# Carrier_for-Addons-V01-004.net
KiCad netlist of a schematic drawn in EAGLE
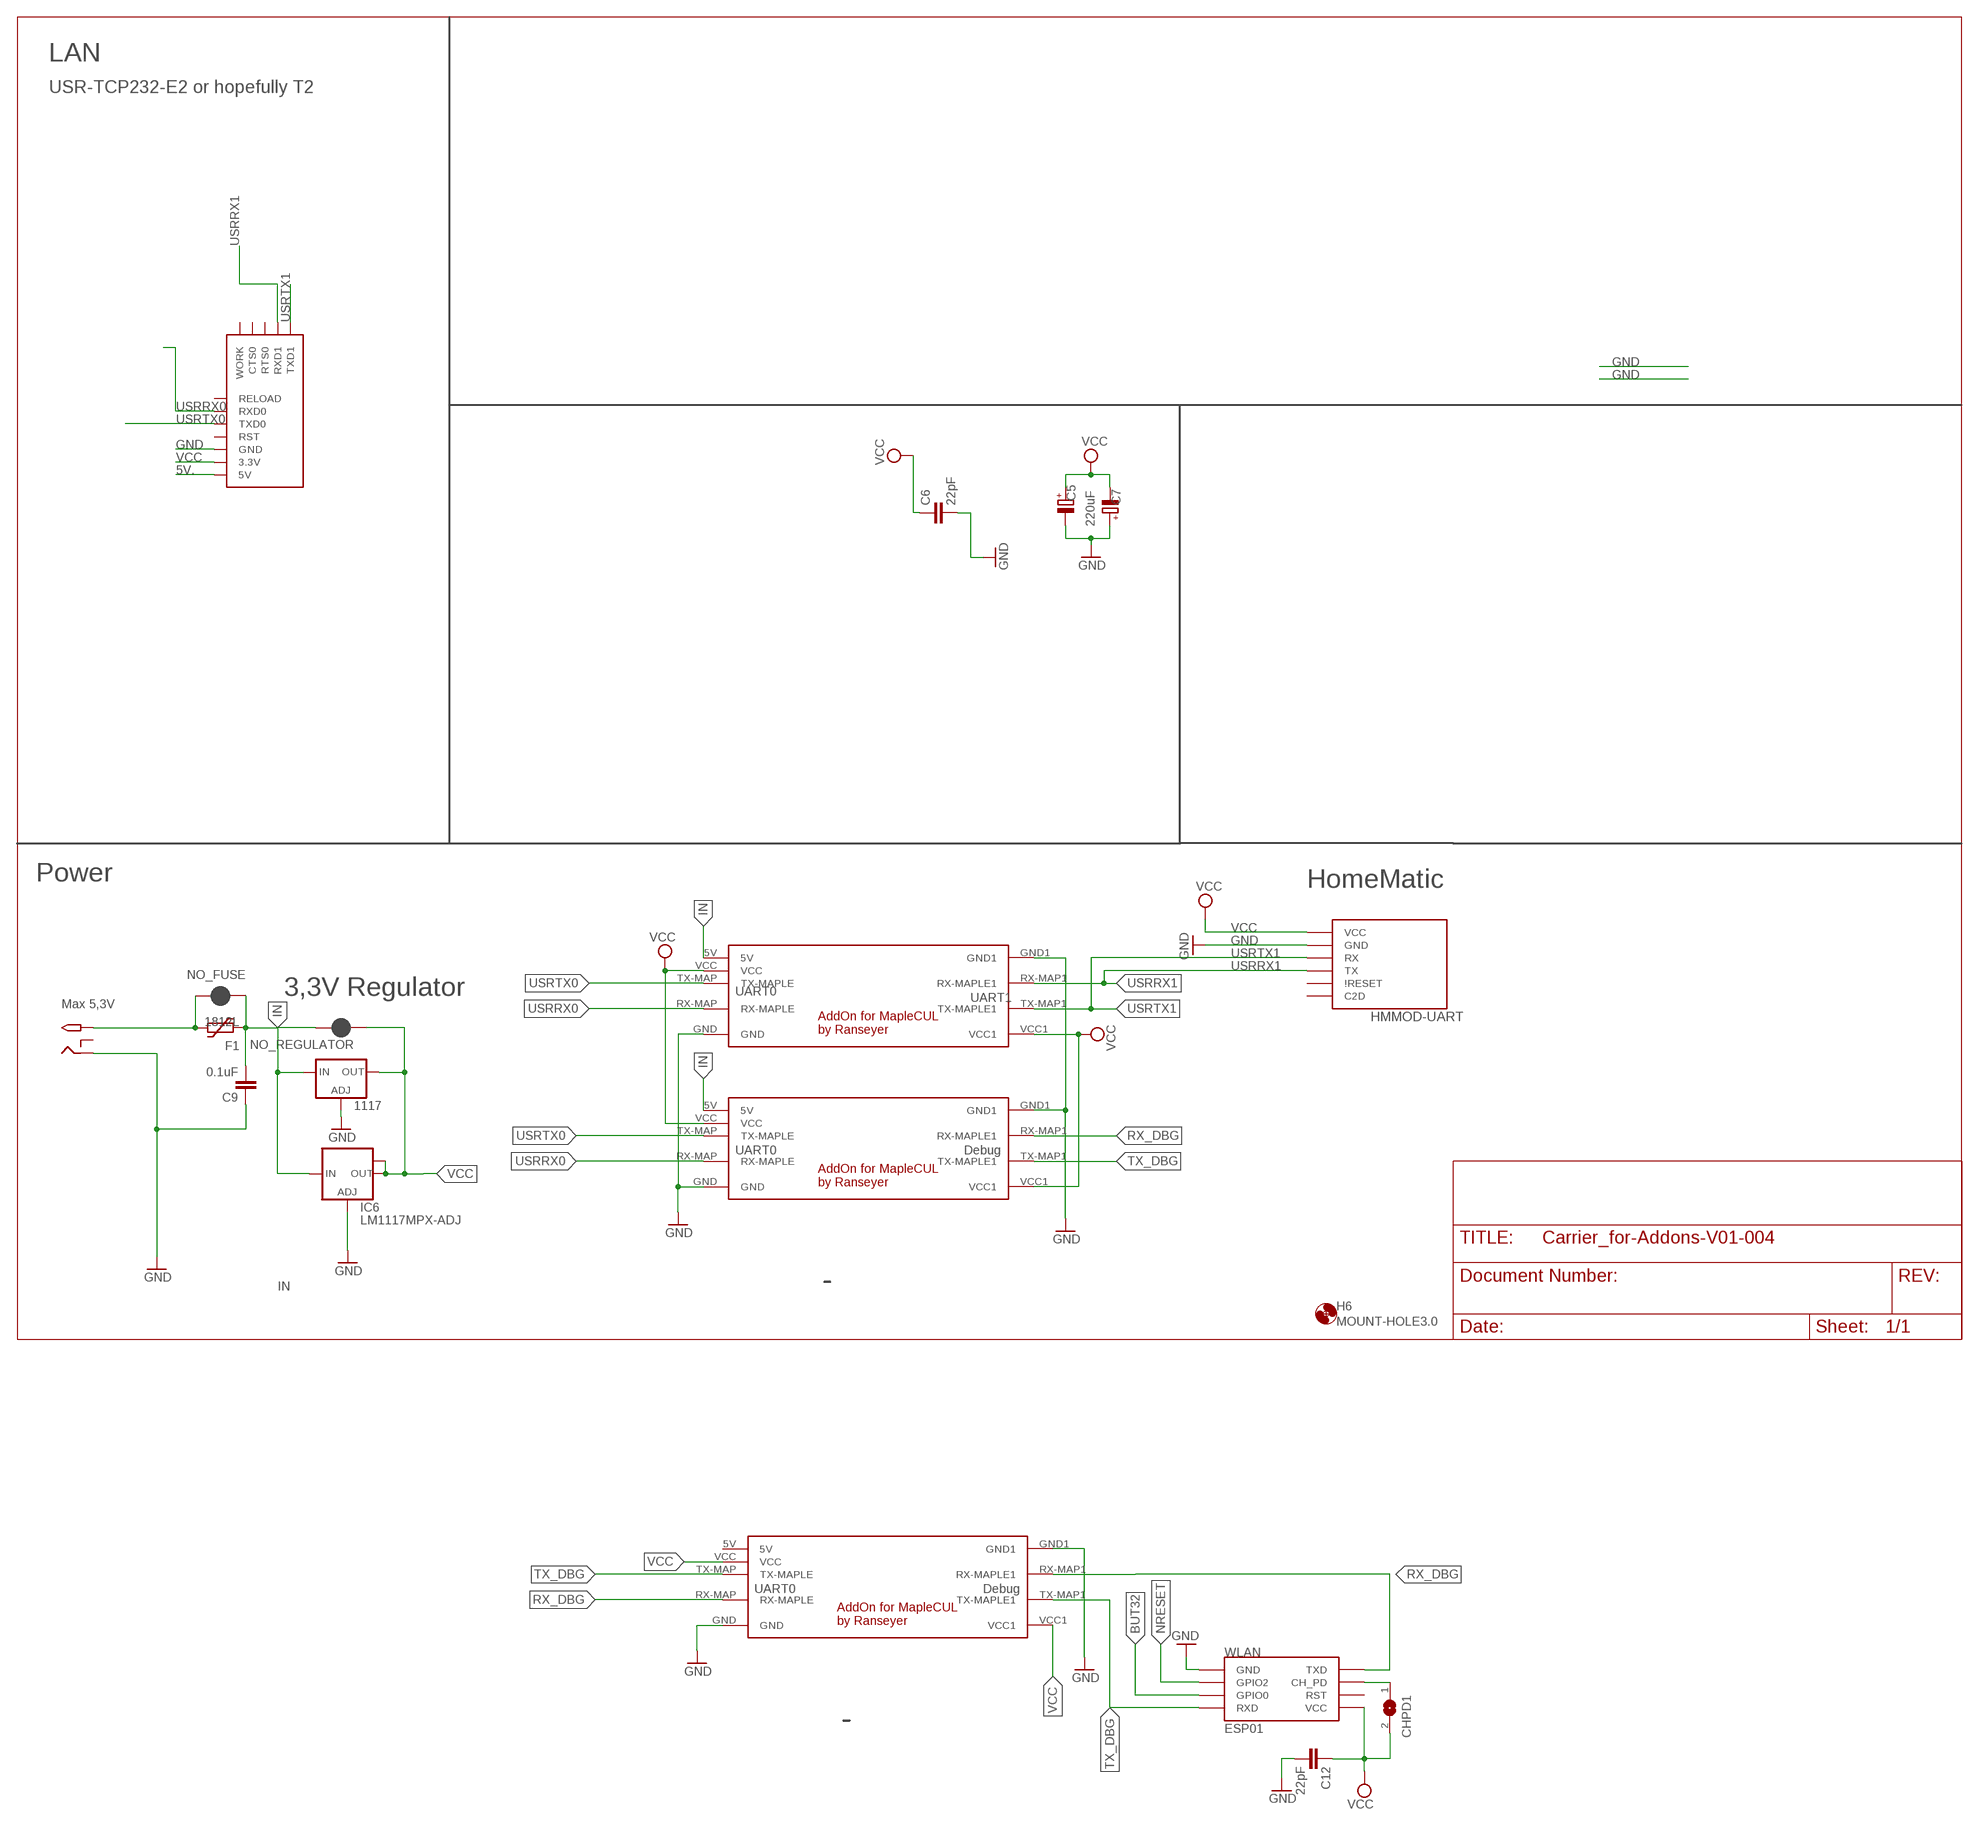
[diagram p0: schematic, sheet 1, part 1 of 2]
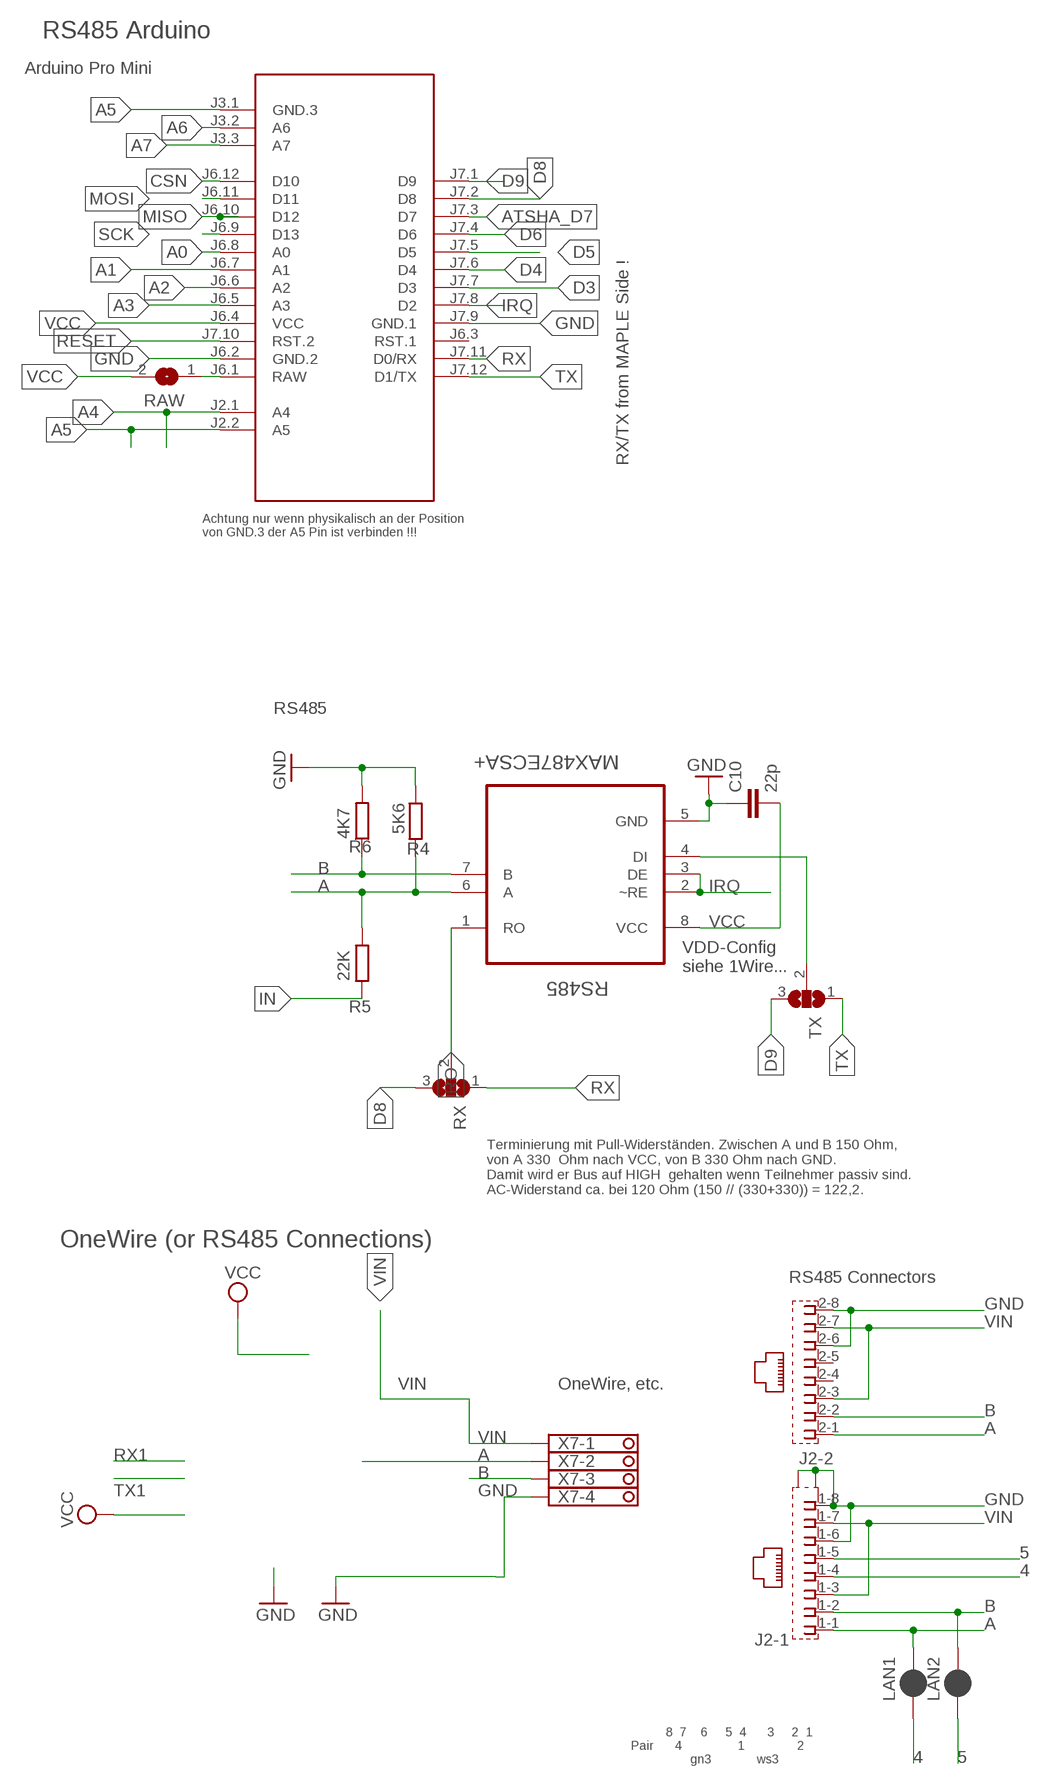
[diagram p1: schematic, sheet 1, part 2 of 2]

(export (version "E")
  (design (tool "Eeschema 10.0.6"))
  (components
    (comp (ref "1117")
      (value "LD117ADT50TR")
      (footprint "eagle-import:DPACK")
      (libsource (lib "eagle-import") (part "LD117A?DT50TR"))
    )
    (comp (ref "C5")
      (value "220uF")
      (footprint "eagle-import:E5-8,5")
      (libsource (lib "eagle-import") (part "CPOL-EUE5-8.5"))
    )
    (comp (ref "C6")
      (value "22pF")
      (footprint "eagle-import:C0805")
      (libsource (lib "eagle-import") (part "C-EUC0805"))
    )
    (comp (ref "C7")
      (value "CPOL-EUSMCE")
      (footprint "eagle-import:SMC_E")
      (libsource (lib "eagle-import") (part "rcl_334_CPOL-EUSMCE"))
    )
    (comp (ref "C9")
      (value "0.1uF")
      (footprint "eagle-import:C1206")
      (libsource (lib "eagle-import") (part "C-EUC1206"))
    )
    (comp (ref "C10")
      (value "22p")
      (footprint "eagle-import:C0805")
      (libsource (lib "eagle-import") (part "C-EUC0805"))
    )
    (comp (ref "C12")
      (value "22pF")
      (footprint "eagle-import:C0805")
      (libsource (lib "eagle-import") (part "C-EUC0805"))
    )
    (comp (ref "CHPD1")
      (value "SJ")
      (footprint "eagle-import:SJ")
      (libsource (lib "eagle-import") (part "jumper_252_SJ"))
    )
    (comp (ref "F1")
      (value "1812L")
      (footprint "eagle-import:1812L")
      (libsource (lib "eagle-import") (part "1812L"))
    )
    (comp (ref "H6")
      (value "MOUNT-HOLE3.0")
      (footprint "eagle-import:3,0")
      (libsource (lib "eagle-import") (part "MOUNT-HOLE3.0"))
    )
    (comp (ref "HMMOD-UART")
      (value "HM-MOD-UARTDIL")
      (footprint "eagle-import:HM-MOD-UART-DIL")
      (libsource (lib "eagle-import") (part "HM-MOD-UARTDIL"))
    )
    (comp (ref "IC6")
      (value "LM1117MPX-ADJ")
      (footprint "eagle-import:SOT223")
      (libsource (lib "eagle-import") (part "LM1117MPX-ADJ"))
    )
    (comp (ref "J2")
      (value "RJ45_2X_S")
      (footprint "eagle-import:RJ45_2X_S")
      (libsource (lib "eagle-import") (part "RJ45_2X_S"))
    )
    (comp (ref "LAN1")
      (value "JUMPER-SMT_2_NC_PASTE_SILK")
      (footprint "eagle-import:SMT-JUMPER_2_NC_PASTE_SILK")
      (libsource (lib "eagle-import") (part "JUMPER-SMT_2_NC_PASTE_SILK"))
    )
    (comp (ref "LAN2")
      (value "JUMPER-SMT_2_NC_PASTE_SILK")
      (footprint "eagle-import:SMT-JUMPER_2_NC_PASTE_SILK")
      (libsource (lib "eagle-import") (part "JUMPER-SMT_2_NC_PASTE_SILK"))
    )
    (comp (ref "M1")
      (value "ARDUINO-PRO-MINI-3.3V#NP")
      (footprint "eagle-import:ARDUINO-PRO-MINI#NP")
      (libsource (lib "eagle-import") (part "ARDUINO-PRO-MINI-#NP3.3V"))
    )
    (comp (ref "NO_FUSE")
      (value "JUMPER-SMT_2_NC_PASTE_NO-SILK")
      (footprint "eagle-import:SMT-JUMPER_2_NC_PASTE_NO-SILK")
      (libsource (lib "eagle-import") (part "SparkFun-Jumpers_528_JUMPER-SMT_2_NC_PASTE_NO-SILK"))
    )
    (comp (ref "NO_REGULATOR")
      (value "JUMPER-SMT_2_NC_PASTE_NO-SILK")
      (footprint "eagle-import:SMT-JUMPER_2_NC_PASTE_NO-SILK")
      (libsource (lib "eagle-import") (part "SparkFun-Jumpers_528_JUMPER-SMT_2_NC_PASTE_NO-SILK"))
    )
    (comp (ref "R4")
      (value "5K6")
      (footprint "eagle-import:R0805")
      (libsource (lib "eagle-import") (part "R-EU_R0805"))
    )
    (comp (ref "R5")
      (value "22K")
      (footprint "eagle-import:R0805")
      (libsource (lib "eagle-import") (part "R-EU_R0805"))
    )
    (comp (ref "R6")
      (value "4K7")
      (footprint "eagle-import:R0805")
      (libsource (lib "eagle-import") (part "R-EU_R0805"))
    )
    (comp (ref "RAW") (value "SJ") (footprint "eagle-import:SJ") (libsource (lib "eagle-import") (part "SJ")))
    (comp (ref "RS485")
      (value "MAX487ECSA+")
      (footprint "eagle-import:SOIC127P600X175-8N")
      (libsource (lib "eagle-import") (part "MAX487ECSA+"))
    )
    (comp (ref "RX")
      (value "SJ2W")
      (footprint "eagle-import:SJ_2")
      (libsource (lib "eagle-import") (part "SJ2W"))
    )
    (comp (ref "TX")
      (value "SJ2W")
      (footprint "eagle-import:SJ_2")
      (libsource (lib "eagle-import") (part "SJ2W"))
    )
    (comp (ref "U$1")
      (value "MAPLE-CUL-ADDON-V01")
      (footprint "eagle-import:MAPLE-CUL-V01")
      (libsource (lib "eagle-import") (part "MAPLE-CUL-ADDON-V01"))
    )
    (comp (ref "U$2")
      (value "2.1MMJACKTHM")
      (footprint "eagle-import:PJ-102A")
      (libsource (lib "eagle-import") (part "2.1MMJACKTHM"))
    )
    (comp (ref "U$3")
      (value "MAPLE-CUL-ADDON-V01")
      (footprint "eagle-import:MAPLE-CUL-V01")
      (libsource (lib "eagle-import") (part "MAPLE-CUL-ADDON-V01"))
    )
    (comp (ref "U$4")
      (value "MAPLE-CUL-ADDON-V01")
      (footprint "eagle-import:MAPLE-CUL-V01")
      (libsource (lib "eagle-import") (part "MAPLE-CUL-ADDON-V01"))
    )
    (comp (ref "U$5")
      (value "USR-TCP232-E2")
      (footprint "eagle-import:USR-TCP232-E2")
      (libsource (lib "eagle-import") (part "USR-TCP232-E2"))
    )
    (comp (ref "WLAN")
      (value "ESP01")
      (footprint "eagle-import:ESP01")
      (libsource (lib "eagle-import") (part "ESP01"))
    )
    (comp (ref "X7")
      (value "1751264")
      (footprint "eagle-import:1751264")
      (libsource (lib "eagle-import") (part "1751264"))
    )
  )
  (nets
    (net (code "1") (name "/4") (class "Default")
      (node (ref "J2") (pin "1-4") (pinfunction "4_1-4") (pintype "passive"))
      (node (ref "LAN1") (pin "1") (pinfunction "1_1") (pintype "passive"))
    )
    (net (code "2") (name "/5") (class "Default")
      (node (ref "J2") (pin "1-5") (pinfunction "5_1-5") (pintype "passive"))
      (node (ref "LAN2") (pin "1") (pinfunction "1_1") (pintype "passive"))
    )
    (net (code "3") (name "/5V.") (class "Default")
      (node (ref "U$5") (pin "5V") (pinfunction "5V_5V") (pintype "bidirectional"))
    )
    (net (code "4") (name "/A") (class "Default")
      (node (ref "J2") (pin "1-1") (pinfunction "1_1-1") (pintype "passive"))
      (node (ref "J2") (pin "2-1") (pinfunction "1_2-1") (pintype "passive"))
      (node (ref "LAN1") (pin "2") (pinfunction "2_2") (pintype "passive"))
      (node (ref "R4") (pin "2") (pinfunction "2_2") (pintype "passive"))
      (node (ref "R5") (pin "2") (pinfunction "2_2") (pintype "passive"))
      (node (ref "RS485") (pin "6") (pinfunction "A_6") (pintype "bidirectional"))
      (node (ref "X7") (pin "2") (pinfunction "K_2") (pintype "passive"))
    )
    (net (code "5") (name "/B") (class "Default")
      (node (ref "J2") (pin "1-2") (pinfunction "2_1-2") (pintype "passive"))
      (node (ref "J2") (pin "2-2") (pinfunction "2_2-2") (pintype "passive"))
      (node (ref "LAN2") (pin "2") (pinfunction "2_2") (pintype "passive"))
      (node (ref "R6") (pin "1") (pinfunction "1_1") (pintype "passive"))
      (node (ref "RS485") (pin "7") (pinfunction "B_7") (pintype "bidirectional"))
      (node (ref "X7") (pin "3") (pinfunction "K_3") (pintype "passive"))
    )
    (net (code "8") (name "A0") (class "Default")
      (node (ref "M1") (pin "J6.8") (pinfunction "A0_J6.8") (pintype "bidirectional"))
    )
    (net (code "9") (name "A1") (class "Default")
      (node (ref "M1") (pin "J6.7") (pinfunction "A1_J6.7") (pintype "bidirectional"))
    )
    (net (code "10") (name "A2") (class "Default")
      (node (ref "M1") (pin "J6.6") (pinfunction "A2_J6.6") (pintype "bidirectional"))
    )
    (net (code "11") (name "A3") (class "Default")
      (node (ref "M1") (pin "J6.5") (pinfunction "A3_J6.5") (pintype "bidirectional"))
    )
    (net (code "12") (name "A4") (class "Default")
      (node (ref "M1") (pin "J2.1") (pinfunction "A4_J2.1") (pintype "bidirectional"))
    )
    (net (code "13") (name "A5") (class "Default")
      (node (ref "M1") (pin "J2.2") (pinfunction "A5_J2.2") (pintype "bidirectional"))
      (node (ref "M1") (pin "J3.1") (pinfunction "GND.3_J3.1") (pintype "bidirectional"))
    )
    (net (code "14") (name "A6") (class "Default")
      (node (ref "M1") (pin "J3.2") (pinfunction "A6_J3.2") (pintype "bidirectional"))
    )
    (net (code "15") (name "A7") (class "Default")
      (node (ref "M1") (pin "J3.3") (pinfunction "A7_J3.3") (pintype "bidirectional"))
    )
    (net (code "16") (name "ATSHA_D7") (class "Default")
      (node (ref "M1") (pin "J7.3") (pinfunction "D7_J7.3") (pintype "bidirectional"))
    )
    (net (code "17") (name "BUT32") (class "Default")
      (node (ref "WLAN") (pin "GPIO0") (pinfunction "GPIO0_GPIO0") (pintype "bidirectional"))
    )
    (net (code "18") (name "CSN") (class "Default")
      (node (ref "M1") (pin "J6.12") (pinfunction "D10_J6.12") (pintype "bidirectional"))
    )
    (net (code "19") (name "D3") (class "Default")
      (node (ref "M1") (pin "J7.7") (pinfunction "D3_J7.7") (pintype "bidirectional"))
    )
    (net (code "20") (name "D4") (class "Default")
      (node (ref "M1") (pin "J7.6") (pinfunction "D4_J7.6") (pintype "bidirectional"))
    )
    (net (code "21") (name "D5") (class "Default")
      (node (ref "M1") (pin "J7.5") (pinfunction "D5_J7.5") (pintype "bidirectional"))
    )
    (net (code "22") (name "D6") (class "Default")
      (node (ref "M1") (pin "J7.4") (pinfunction "D6_J7.4") (pintype "bidirectional"))
    )
    (net (code "23") (name "D8") (class "Default")
      (node (ref "M1") (pin "J7.2") (pinfunction "D8_J7.2") (pintype "bidirectional"))
      (node (ref "RX") (pin "3") (pinfunction "3_3") (pintype "passive"))
    )
    (net (code "24") (name "D9") (class "Default")
      (node (ref "M1") (pin "J7.1") (pinfunction "D9_J7.1") (pintype "bidirectional"))
      (node (ref "TX") (pin "3") (pinfunction "3_3") (pintype "passive"))
    )
    (net (code "25") (name "GND") (class "Default")
      (node (ref "1117") (pin "1") (pinfunction "ADJ_1") (pintype "input"))
      (node (ref "C10") (pin "1") (pinfunction "1_1") (pintype "passive"))
      (node (ref "C12") (pin "2") (pinfunction "2_2") (pintype "passive"))
      (node (ref "C5") (pin "-") (pinfunction "-_-") (pintype "passive"))
      (node (ref "C6") (pin "2") (pinfunction "2_2") (pintype "passive"))
      (node (ref "C7") (pin "+") (pinfunction "+_+") (pintype "passive"))
      (node (ref "C9") (pin "1") (pinfunction "1_1") (pintype "passive"))
      (node (ref "HMMOD-UART") (pin "2") (pinfunction "GND_2") (pintype "power_in"))
      (node (ref "IC6") (pin "1") (pinfunction "ADJ_1") (pintype "input"))
      (node (ref "J2") (pin "1-6") (pinfunction "6_1-6") (pintype "passive"))
      (node (ref "J2") (pin "1-8") (pinfunction "8_1-8") (pintype "passive"))
      (node (ref "J2") (pin "2-6") (pinfunction "6_2-6") (pintype "passive"))
      (node (ref "J2") (pin "2-8") (pinfunction "8_2-8") (pintype "passive"))
      (node (ref "J2") (pin "G1") (pinfunction "S2_G1") (pintype "passive"))
      (node (ref "J2") (pin "G3") (pinfunction "S1_G3") (pintype "passive"))
      (node (ref "M1") (pin "J6.2") (pinfunction "GND.2_J6.2") (pintype "power_in"))
      (node (ref "M1") (pin "J7.9") (pinfunction "GND.1_J7.9") (pintype "power_in"))
      (node (ref "R4") (pin "1") (pinfunction "1_1") (pintype "passive"))
      (node (ref "R6") (pin "2") (pinfunction "2_2") (pintype "passive"))
      (node (ref "RS485") (pin "5") (pinfunction "GND_5") (pintype "passive"))
      (node (ref "U$1") (pin "GND") (pinfunction "GND_GND") (pintype "bidirectional"))
      (node (ref "U$1") (pin "GND1") (pinfunction "GND1_GND1") (pintype "bidirectional"))
      (node (ref "U$2") (pin "RING") (pinfunction "RING_RING") (pintype "bidirectional"))
      (node (ref "U$3") (pin "GND") (pinfunction "GND_GND") (pintype "bidirectional"))
      (node (ref "U$3") (pin "GND1") (pinfunction "GND1_GND1") (pintype "bidirectional"))
      (node (ref "U$4") (pin "GND") (pinfunction "GND_GND") (pintype "bidirectional"))
      (node (ref "U$4") (pin "GND1") (pinfunction "GND1_GND1") (pintype "bidirectional"))
      (node (ref "U$5") (pin "GND") (pinfunction "GND_GND") (pintype "bidirectional"))
      (node (ref "WLAN") (pin "GND") (pinfunction "GND_GND") (pintype "bidirectional"))
      (node (ref "X7") (pin "4") (pinfunction "K_4") (pintype "passive"))
    )
    (net (code "26") (name "IN") (class "Default")
      (node (ref "1117") (pin "3") (pinfunction "IN_3") (pintype "input"))
      (node (ref "C9") (pin "2") (pinfunction "2_2") (pintype "passive"))
      (node (ref "F1") (pin "P$1") (pinfunction "1_P$1") (pintype "passive"))
      (node (ref "IC6") (pin "3") (pinfunction "IN_3") (pintype "input"))
      (node (ref "NO_FUSE") (pin "1") (pinfunction "1_1") (pintype "passive"))
      (node (ref "NO_REGULATOR") (pin "2") (pinfunction "2_2") (pintype "passive"))
      (node (ref "R5") (pin "1") (pinfunction "1_1") (pintype "passive"))
      (node (ref "U$3") (pin "5V") (pinfunction "5V_5V") (pintype "bidirectional"))
      (node (ref "U$4") (pin "5V") (pinfunction "5V_5V") (pintype "bidirectional"))
    )
    (net (code "27") (name "IRQ") (class "Default")
      (node (ref "M1") (pin "J7.8") (pinfunction "D2_J7.8") (pintype "bidirectional"))
      (node (ref "RS485") (pin "2") (pinfunction "~{RE}_2") (pintype "input"))
      (node (ref "RS485") (pin "3") (pinfunction "DE_3") (pintype "input"))
    )
    (net (code "28") (name "MISO") (class "Default")
      (node (ref "M1") (pin "J6.10") (pinfunction "D12_J6.10") (pintype "bidirectional"))
    )
    (net (code "29") (name "MOSI") (class "Default")
      (node (ref "M1") (pin "J6.11") (pinfunction "D11_J6.11") (pintype "bidirectional"))
    )
    (net (code "30") (name "NRESET") (class "Default")
      (node (ref "WLAN") (pin "GPIO2") (pinfunction "GPIO2_GPIO2") (pintype "bidirectional"))
    )
    (net (code "31") (name "Net-(CHPD1-Pad1)") (class "Default")
      (node (ref "CHPD1") (pin "1") (pinfunction "1_1") (pintype "passive"))
      (node (ref "WLAN") (pin "CH_PD") (pinfunction "CH_PD_CH_PD") (pintype "bidirectional"))
    )
    (net (code "32") (name "Net-(M1-RAW)") (class "Default")
      (node (ref "M1") (pin "J6.1") (pinfunction "RAW_J6.1") (pintype "power_in"))
      (node (ref "RAW") (pin "1") (pinfunction "1_1") (pintype "passive"))
    )
    (net (code "33") (name "Net-(RS485-DI)") (class "Default")
      (node (ref "RS485") (pin "4") (pinfunction "DI_4") (pintype "input"))
      (node (ref "TX") (pin "2") (pinfunction "2_2") (pintype "passive"))
    )
    (net (code "34") (name "RESET") (class "Default")
      (node (ref "M1") (pin "J7.10") (pinfunction "RST.2_J7.10") (pintype "bidirectional"))
    )
    (net (code "35") (name "RO") (class "Default")
      (node (ref "RS485") (pin "1") (pinfunction "RO_1") (pintype "output"))
      (node (ref "RX") (pin "2") (pinfunction "2_2") (pintype "passive"))
    )
    (net (code "36") (name "RX") (class "Default")
      (node (ref "M1") (pin "J7.11") (pinfunction "D0/RX_J7.11") (pintype "bidirectional"))
      (node (ref "RX") (pin "1") (pinfunction "1_1") (pintype "passive"))
    )
    (net (code "37") (name "RX_DBG") (class "Default")
      (node (ref "U$1") (pin "RX-MAP") (pinfunction "RX-MAPLE_RX-MAP") (pintype "bidirectional"))
      (node (ref "U$1") (pin "RX-MAP1") (pinfunction "RX-MAPLE1_RX-MAP1") (pintype "bidirectional"))
      (node (ref "U$4") (pin "RX-MAP1") (pinfunction "RX-MAPLE1_RX-MAP1") (pintype "bidirectional"))
      (node (ref "WLAN") (pin "TX") (pinfunction "TXD_TX") (pintype "bidirectional"))
    )
    (net (code "38") (name "SCK") (class "Default")
      (node (ref "M1") (pin "J6.9") (pinfunction "D13_J6.9") (pintype "bidirectional"))
    )
    (net (code "39") (name "TX") (class "Default")
      (node (ref "M1") (pin "J7.12") (pinfunction "D1/TX_J7.12") (pintype "bidirectional"))
      (node (ref "TX") (pin "1") (pinfunction "1_1") (pintype "passive"))
    )
    (net (code "40") (name "TX_DBG") (class "Default")
      (node (ref "U$1") (pin "TX-MAP") (pinfunction "TX-MAPLE_TX-MAP") (pintype "bidirectional"))
      (node (ref "U$1") (pin "TX-MAP1") (pinfunction "TX-MAPLE1_TX-MAP1") (pintype "bidirectional"))
      (node (ref "U$4") (pin "TX-MAP1") (pinfunction "TX-MAPLE1_TX-MAP1") (pintype "bidirectional"))
      (node (ref "WLAN") (pin "RX") (pinfunction "RXD_RX") (pintype "bidirectional"))
    )
    (net (code "41") (name "USRRX0") (class "Default")
      (node (ref "U$3") (pin "RX-MAP") (pinfunction "RX-MAPLE_RX-MAP") (pintype "bidirectional"))
      (node (ref "U$4") (pin "RX-MAP") (pinfunction "RX-MAPLE_RX-MAP") (pintype "bidirectional"))
      (node (ref "U$5") (pin "RXD0") (pinfunction "RXD0_RXD0") (pintype "input"))
    )
    (net (code "42") (name "USRRX1") (class "Default")
      (node (ref "HMMOD-UART") (pin "5") (pinfunction "TX_5") (pintype "bidirectional"))
      (node (ref "U$3") (pin "RX-MAP1") (pinfunction "RX-MAPLE1_RX-MAP1") (pintype "bidirectional"))
      (node (ref "U$5") (pin "RXD1") (pinfunction "RXD1_RXD1") (pintype "input"))
    )
    (net (code "43") (name "USRTX0") (class "Default")
      (node (ref "U$3") (pin "TX-MAP") (pinfunction "TX-MAPLE_TX-MAP") (pintype "bidirectional"))
      (node (ref "U$4") (pin "TX-MAP") (pinfunction "TX-MAPLE_TX-MAP") (pintype "bidirectional"))
      (node (ref "U$5") (pin "TXD0") (pinfunction "TXD0_TXD0") (pintype "output"))
    )
    (net (code "44") (name "USRTX1") (class "Default")
      (node (ref "HMMOD-UART") (pin "6") (pinfunction "RX_6") (pintype "bidirectional"))
      (node (ref "U$3") (pin "TX-MAP1") (pinfunction "TX-MAPLE1_TX-MAP1") (pintype "bidirectional"))
      (node (ref "U$5") (pin "TXD1") (pinfunction "TXD1_TXD1") (pintype "output"))
    )
    (net (code "45") (name "VCC") (class "Default")
      (node (ref "1117") (pin "4") (pinfunction "OUT_4") (pintype "passive"))
      (node (ref "C10") (pin "2") (pinfunction "2_2") (pintype "passive"))
      (node (ref "C12") (pin "1") (pinfunction "1_1") (pintype "passive"))
      (node (ref "C5") (pin "+") (pinfunction "+_+") (pintype "passive"))
      (node (ref "C6") (pin "1") (pinfunction "1_1") (pintype "passive"))
      (node (ref "C7") (pin "-") (pinfunction "-_-") (pintype "passive"))
      (node (ref "CHPD1") (pin "2") (pinfunction "2_2") (pintype "passive"))
      (node (ref "HMMOD-UART") (pin "1") (pinfunction "VCC_1") (pintype "power_in"))
      (node (ref "IC6") (pin "2") (pinfunction "OUT_2") (pintype "passive"))
      (node (ref "IC6") (pin "TAB") (pinfunction "OUT1_TAB") (pintype "passive"))
      (node (ref "M1") (pin "J6.4") (pinfunction "VCC_J6.4") (pintype "power_in"))
      (node (ref "NO_REGULATOR") (pin "1") (pinfunction "1_1") (pintype "passive"))
      (node (ref "RAW") (pin "2") (pinfunction "2_2") (pintype "passive"))
      (node (ref "RS485") (pin "8") (pinfunction "VCC_8") (pintype "power_in"))
      (node (ref "U$1") (pin "VCC") (pinfunction "VCC_VCC") (pintype "bidirectional"))
      (node (ref "U$1") (pin "VCC1") (pinfunction "VCC1_VCC1") (pintype "bidirectional"))
      (node (ref "U$3") (pin "VCC") (pinfunction "VCC_VCC") (pintype "bidirectional"))
      (node (ref "U$3") (pin "VCC1") (pinfunction "VCC1_VCC1") (pintype "bidirectional"))
      (node (ref "U$4") (pin "VCC") (pinfunction "VCC_VCC") (pintype "bidirectional"))
      (node (ref "U$4") (pin "VCC1") (pinfunction "VCC1_VCC1") (pintype "bidirectional"))
      (node (ref "U$5") (pin "3.3V") (pinfunction "3.3V_3.3V") (pintype "bidirectional"))
      (node (ref "WLAN") (pin "VCC") (pinfunction "VCC_VCC") (pintype "bidirectional"))
    )
    (net (code "46") (name "VIN") (class "Default")
      (node (ref "F1") (pin "P$2") (pinfunction "2_P$2") (pintype "passive"))
      (node (ref "J2") (pin "1-3") (pinfunction "3_1-3") (pintype "passive"))
      (node (ref "J2") (pin "1-7") (pinfunction "7_1-7") (pintype "passive"))
      (node (ref "J2") (pin "2-3") (pinfunction "3_2-3") (pintype "passive"))
      (node (ref "J2") (pin "2-7") (pinfunction "7_2-7") (pintype "passive"))
      (node (ref "NO_FUSE") (pin "2") (pinfunction "2_2") (pintype "passive"))
      (node (ref "U$2") (pin "TIP") (pinfunction "TIP_TIP") (pintype "bidirectional"))
      (node (ref "X7") (pin "1") (pinfunction "K_1") (pintype "passive"))
    )
    (net (code "47") (name "unconnected-(HMMOD-UART-C2D-Pad3)") (class "Default")
      (node (ref "HMMOD-UART") (pin "3") (pinfunction "C2D_3") (pintype "bidirectional"))
    )
    (net (code "48") (name "unconnected-(HMMOD-UART-\\~{RESET}-Pad4)") (class "Default")
      (node (ref "HMMOD-UART") (pin "4") (pinfunction "\\~{RESET}_4") (pintype "bidirectional"))
    )
    (net (code "49") (name "unconnected-(J2B-4-Pad2-4)") (class "Default")
      (node (ref "J2") (pin "2-4") (pinfunction "4_2-4") (pintype "passive"))
    )
    (net (code "50") (name "unconnected-(J2B-5-Pad2-5)") (class "Default")
      (node (ref "J2") (pin "2-5") (pinfunction "5_2-5") (pintype "passive"))
    )
    (net (code "51") (name "unconnected-(M1-RST.1-PadJ6.3)") (class "Default")
      (node (ref "M1") (pin "J6.3") (pinfunction "RST.1_J6.3") (pintype "bidirectional"))
    )
    (net (code "52") (name "unconnected-(U$1-Pad5V)") (class "Default")
      (node (ref "U$1") (pin "5V") (pinfunction "5V_5V") (pintype "bidirectional"))
    )
    (net (code "53") (name "unconnected-(U$2-PadRING_SW)") (class "Default")
      (node (ref "U$2") (pin "RING_SW") (pinfunction "RING_SW_RING_SW") (pintype "bidirectional"))
    )
    (net (code "54") (name "unconnected-(U$5-PadCTS0)") (class "Default")
      (node (ref "U$5") (pin "CTS0") (pinfunction "CTS0_CTS0") (pintype "bidirectional"))
    )
    (net (code "55") (name "unconnected-(U$5-PadRELOAD)") (class "Default")
      (node (ref "U$5") (pin "RELOAD") (pinfunction "RELOAD_RELOAD") (pintype "bidirectional"))
    )
    (net (code "56") (name "unconnected-(U$5-PadRST)") (class "Default")
      (node (ref "U$5") (pin "RST") (pinfunction "RST_RST") (pintype "bidirectional"))
    )
    (net (code "57") (name "unconnected-(U$5-PadRTS0)") (class "Default")
      (node (ref "U$5") (pin "RTS0") (pinfunction "RTS0_RTS0") (pintype "bidirectional"))
    )
    (net (code "58") (name "unconnected-(U$5-PadWORK)") (class "Default")
      (node (ref "U$5") (pin "WORK") (pinfunction "WORK_WORK") (pintype "bidirectional"))
    )
    (net (code "59") (name "unconnected-(WLAN-PadRST)") (class "Default")
      (node (ref "WLAN") (pin "RST") (pinfunction "RST_RST") (pintype "bidirectional"))
    )
  )
)
